# Power_Supplies.net
KiCad netlist of a schematic drawn in Altium Designer
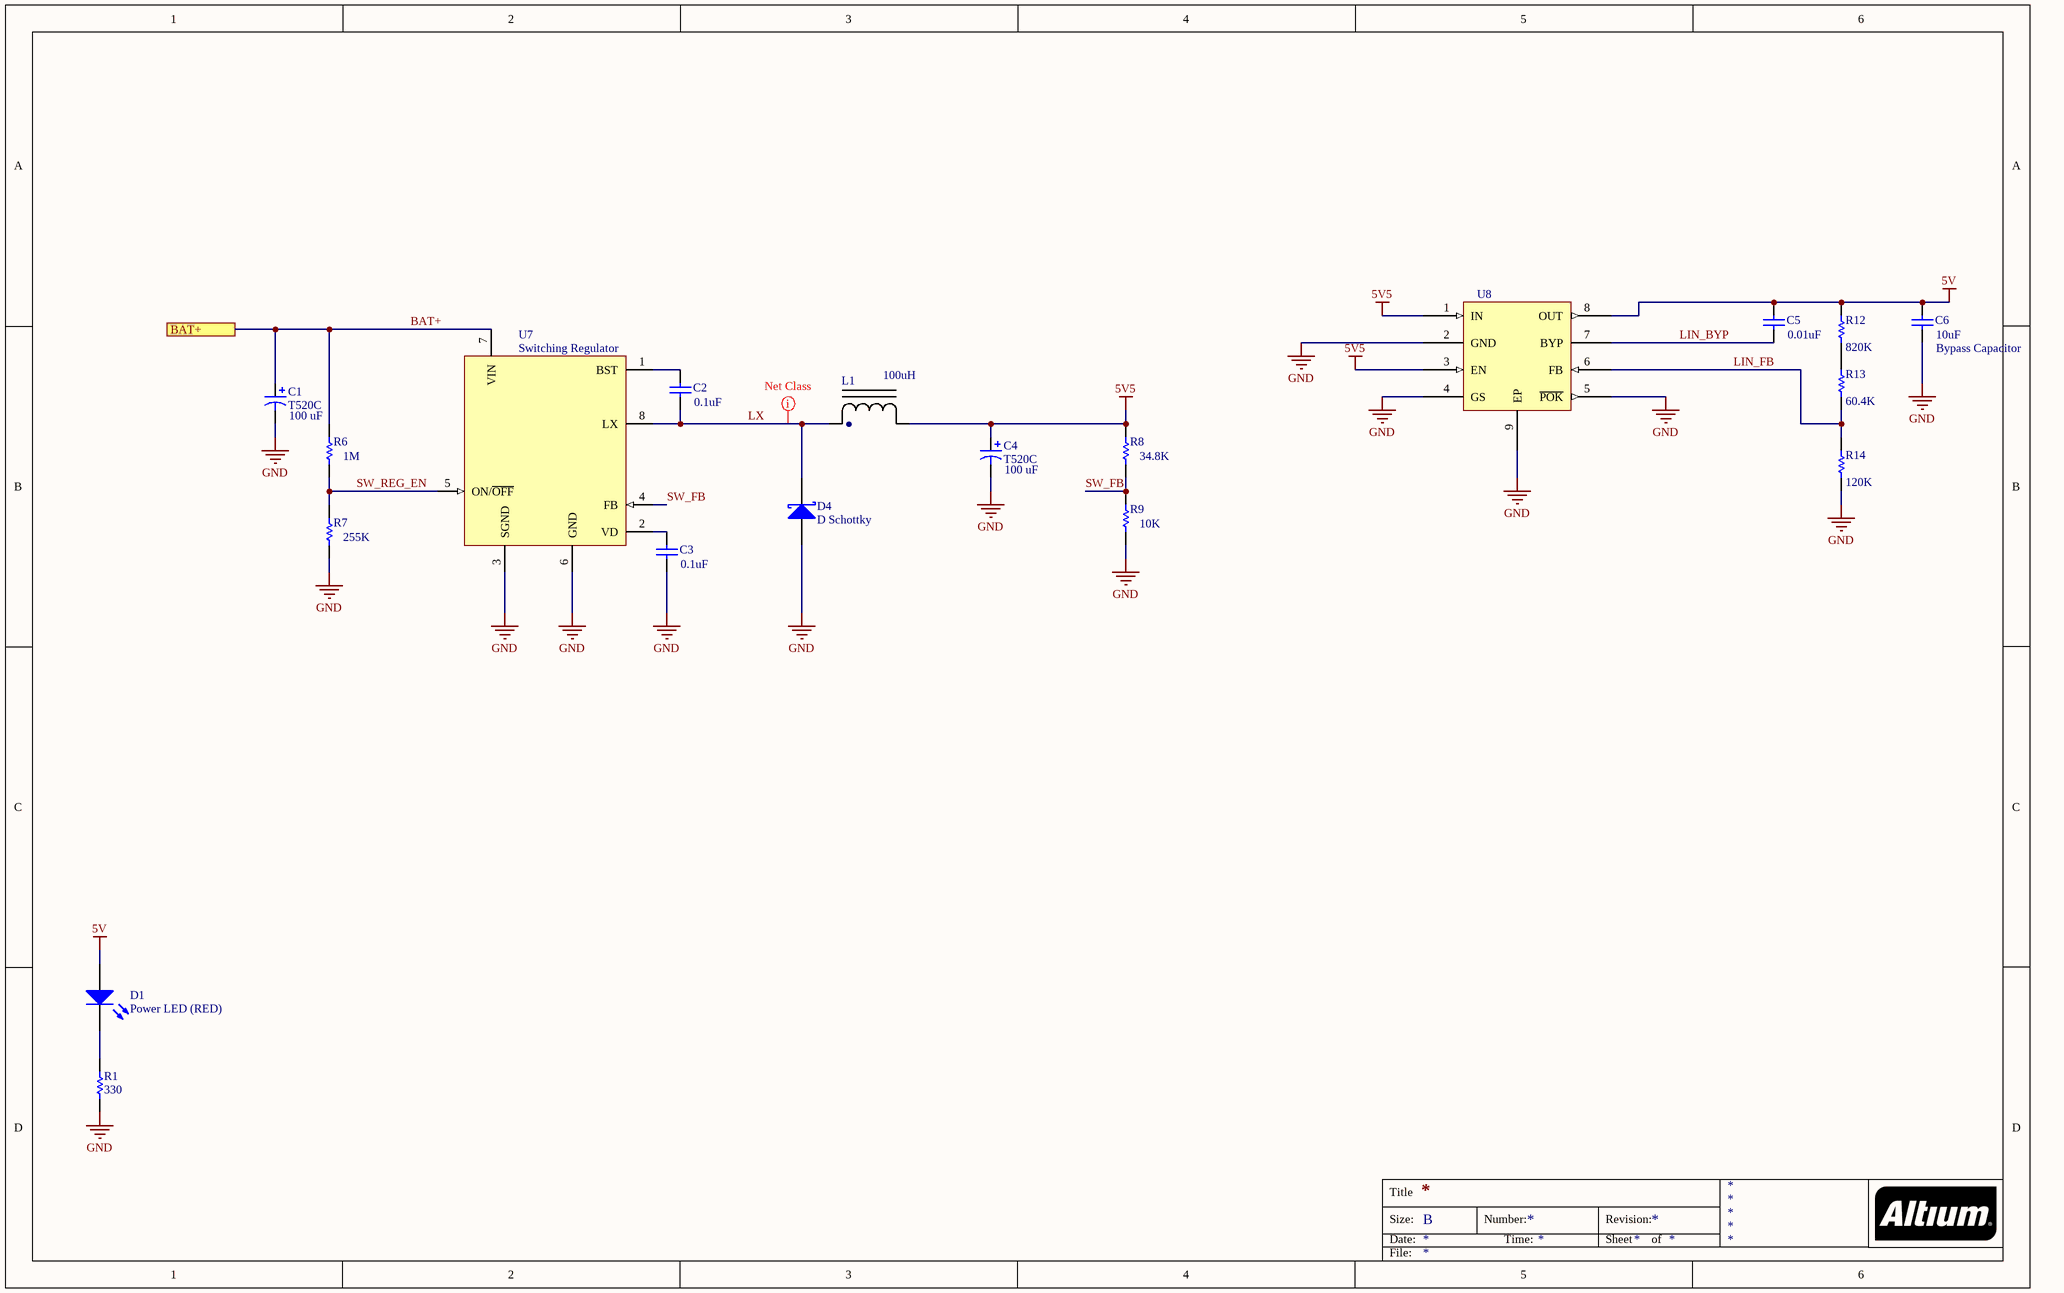
[diagram p0: Power_Supplies.SchDoc]

(export (version "E")
  (design (tool "Eeschema 10.0.6"))
  (components
    (comp (ref "C1")
      (value "T520C")
      (footprint "C")
      (description "Tantalum Capacitors - Polymer SMD 6.3volts 100uF 20% ESR=5mOhms")
      (fields
        (field (name "MANUFACTURER") "KEMET")
        (field (name "TOLERANCE") "20 %")
        (field (name "ALTIUM_VALUE") "100 uF")
      )
      (libsource (lib "KEMET Chip Capacitor") (part "T520D"))
    )
    (comp (ref "C2")
      (value "0.1uF")
      (footprint "1608[0603]")
      (description "Multilayer Ceramic Capacitors MLCC - SMD/SMT 0603 .1uF 50volts X7R 10%")
      (fields
        (field (name "MANUFACTURER PART NUMBER") "VJ0603Y104KXAAC")
        (field (name "MANUFACTURER") "Vishay Semiconductors")
      )
      (libsource (lib "Miscellaneous Devices") (part "Cap"))
    )
    (comp (ref "C3")
      (value "0.1uF")
      (footprint "1608[0603]")
      (description "Multilayer Ceramic Capacitors MLCC - SMD/SMT 0603 .1uF 50volts X7R 10%")
      (fields
        (field (name "MANUFACTURER PART NUMBER") "VJ0603Y104KXAAC")
        (field (name "MANUFACTURER") "Vishay Semiconductors")
      )
      (libsource (lib "Miscellaneous Devices") (part "Cap"))
    )
    (comp (ref "C4")
      (value "T520C")
      (footprint "C")
      (description "Tantalum Capacitors - Polymer SMD 6.3volts 100uF 20% ESR=5mOhms")
      (fields
        (field (name "MANUFACTURER") "KEMET")
        (field (name "TOLERANCE") "20 %")
        (field (name "ALTIUM_VALUE") "100 uF")
      )
      (libsource (lib "KEMET Chip Capacitor") (part "T520D"))
    )
    (comp (ref "C5")
      (value "0.01uF")
      (footprint "1608[0603]")
      (description "Multilayer Ceramic Capacitors MLCC - SMD/SMT 50volts 10000pF X7R 5%")
      (fields
        (field (name "MANUFACTURER PART NUMBER") "C0603C103J5RALTU")
        (field (name "MANUFACTURER") "KEMET")
      )
      (libsource (lib "Miscellaneous Devices") (part "Cap"))
    )
    (comp (ref "C6")
      (value "Bypass Capacitor")
      (footprint "C1206")
      (description "Multilayer Ceramic Capacitors MLCC - SMD/SMT SOFT 1206 25V 10uF X7R 20% T: 1.6mm")
      (fields
        (field (name "ALTIUM_VALUE") "10uF")
        (field (name "MANUFACTURER PART NUMBER") "C3216X7R1E106M160AE")
        (field (name "MANUFACTURER") "TDK")
      )
      (libsource (lib "Miscellaneous Devices") (part "Cap"))
    )
    (comp (ref "D1")
      (value "Power LED (RED)")
      (footprint "1608[0603]")
      (description "Standard LEDs - SMD Super Red, 660nm 1.7V, 45mcd")
      (fields
        (field (name "MANUFACTURER PART NUMBER") "SML-LX0603SRW-TR")
        (field (name "MANUFACTURER") "Lumex")
      )
      (libsource (lib "Miscellaneous Devices") (part "LED0"))
    )
    (comp (ref "D4")
      (value "D Schottky")
      (footprint "SOD123")
      (description "Schottky Diodes & Rectifiers Schottky Power Rect .5a")
      (fields
        (field (name "MANUFACTURER PART NUMBER") "MBR0520L")
        (field (name "MANUFACTURER") "ON Semiconductor / Fairchild")
      )
      (libsource (lib "Miscellaneous Devices") (part "D Schottky"))
    )
    (comp (ref "L1")
      (value "100uH")
      (footprint "UP1B")
      (description "Fixed Inductors 100uH 0.53A 1.11ohms")
      (fields (field (name "TOLERANCE") "20%") (field (name "MANUFACTURER") "Eaton"))
      (libsource (lib "Eaton_Power_Inductors") (part "UP1B-100-R"))
    )
    (comp (ref "R1")
      (value "330")
      (footprint "1608[0603]")
      (description "Thick Film Resistors - SMD 330 ohm 0.5% 0.33W AEC-Q200")
      (fields
        (field (name "MANUFACTURER") "KOA Speer")
        (field (name "MANUFACTURER PART NUMBER") "SG73G1JTTD3300D")
      )
      (libsource (lib "Miscellaneous Devices") (part "Res1"))
    )
    (comp (ref "R6")
      (value "1M")
      (footprint "1608[0603]")
      (description "Thin Film Resistors - SMD 1M OHM .1% 25PPM")
      (fields (field (name "TOLERANCE") "0.1%") (field (name "MANUFACTURER PART NUMBER") "RT0603BRD071ML"))
      (libsource (lib "Miscellaneous Devices") (part "Res1"))
    )
    (comp (ref "R7")
      (value "255K")
      (footprint "1608[0603]")
      (description "Thin Film Resistors - SMD 255Kohms .1% 25ppm")
      (fields (field (name "MANUFACTURER") "Vishay Dale") (field (name "TOLERANCE") "0.1%"))
      (libsource (lib "Miscellaneous Devices") (part "Res1"))
    )
    (comp (ref "R8")
      (value "34.8K")
      (footprint "1608[0603]")
      (description "Thin Film Resistors - SMD 150mW 34.8kohm 0.1% 25PPM 0603")
      (fields (field (name "TOLERANCE") "0.1 %") (field (name "MANUFACTURER") "Vishay"))
      (libsource (lib "Miscellaneous Devices") (part "Res1"))
    )
    (comp (ref "R9")
      (value "10K")
      (footprint "1608[0603]")
      (description "Thin Film Resistors - SMD 150mW 10kohm 0.1% 25PPM 0603")
      (fields (field (name "MANUFACTURER") "Vishay") (field (name "TOLERANCE") "0.1 %"))
      (libsource (lib "Miscellaneous Devices") (part "Res1"))
    )
    (comp (ref "R12")
      (value "820K")
      (footprint "1608[0603]")
      (description "Thin Film Resistors - SMD CPF0603 820K 0.1% 25PPM 5K RL")
      (fields
        (field (name "MANUFACTURER") "TE Connectivity")
        (field (name "MANUFACTURER PART NUMBER") "CPF0603B820KE")
      )
      (libsource (lib "Miscellaneous Devices") (part "Res1"))
    )
    (comp (ref "R13")
      (value "60.4K")
      (footprint "1608[0603]")
      (description "Thin Film Resistors - SMD .063W 60.4K ohm 0.1% 25ppm")
      (fields (field (name "TOLERANCE") "0.1%") (field (name "MANUFACTURER") "TT Welwyn"))
      (libsource (lib "Miscellaneous Devices") (part "Res1"))
    )
    (comp (ref "R14")
      (value "120K")
      (footprint "1608[0603]")
      (description "Thin Film Resistors - SMD CPF 0603 120K 0.1% 25PPM 1K RL")
      (fields (field (name "MANUFACTURER PART NUMBER") "CPF0603B120KE1") (field (name "TOLERANCE") "0.1%"))
      (libsource (lib "Miscellaneous Devices") (part "Res1"))
    )
    (comp (ref "U7")
      (value "Switching Regulator")
      (footprint "SOIC8_N")
      (description "Switching Voltage Regulators 1A 76V MAXPower Step-Down")
      (fields (field (name "MANUFACTURER") "Maxim") (field (name "MANUFACTURER PART NUMBER") "MAX5035DASA+T"))
      (libsource (lib "Maxim_Integrated_Switching_Regulators") (part "MAX5035"))
    )
    (comp (ref "U8")
      (value "MAX8902BATA+T")
      (footprint "8 TDFN-EP")
      (description "LDO Voltage Regulators 500mA LDO Regulator")
      (fields
        (field (name "MANUFACTURER") "Maxim Integrated")
        (field (name "MANUFACTURER PART NUMBER") "MAX8902AATA+T")
      )
      (libsource (lib "Maxim_Integrated_Linear_Regulators") (part "MAX8902BATA+T"))
    )
  )
  (nets
    (net (code "1") (name "/BAT+") (class "Default")
      (node (ref "C1") (pin "1") (pinfunction "1_1") (pintype "passive"))
      (node (ref "R6") (pin "2") (pinfunction "2_2") (pintype "passive"))
      (node (ref "U7") (pin "7") (pinfunction "VIN_7") (pintype "power_in"))
    )
    (net (code "2") (name "/LIN_BYP") (class "Default")
      (node (ref "C5") (pin "1") (pinfunction "1_1") (pintype "passive"))
      (node (ref "U8") (pin "7") (pinfunction "BYP_7") (pintype "passive"))
    )
    (net (code "3") (name "/LIN_FB") (class "Default")
      (node (ref "R13") (pin "1") (pinfunction "1_1") (pintype "passive"))
      (node (ref "R14") (pin "2") (pinfunction "2_2") (pintype "passive"))
      (node (ref "U8") (pin "6") (pinfunction "FB_6") (pintype "input"))
    )
    (net (code "4") (name "/LX") (class "Default")
      (node (ref "C2") (pin "2") (pinfunction "2_2") (pintype "passive"))
      (node (ref "D4") (pin "2") (pinfunction "A_2") (pintype "passive"))
      (node (ref "L1") (pin "1") (pintype "passive"))
      (node (ref "U7") (pin "8") (pinfunction "LX_8") (pintype "passive"))
    )
    (net (code "5") (name "/SW_FB") (class "Default")
      (node (ref "R8") (pin "1") (pinfunction "1_1") (pintype "passive"))
      (node (ref "R9") (pin "2") (pinfunction "2_2") (pintype "passive"))
      (node (ref "U7") (pin "4") (pinfunction "FB_4") (pintype "input"))
    )
    (net (code "6") (name "/SW_REG_EN") (class "Default")
      (node (ref "R6") (pin "1") (pinfunction "1_1") (pintype "passive"))
      (node (ref "R7") (pin "2") (pinfunction "2_2") (pintype "passive"))
      (node (ref "U7") (pin "5") (pinfunction "ON/~{OFF}_5") (pintype "input"))
    )
    (net (code "7") (name "5V") (class "Default")
      (node (ref "C5") (pin "2") (pinfunction "2_2") (pintype "passive"))
      (node (ref "C6") (pin "2") (pinfunction "2_2") (pintype "passive"))
      (node (ref "D1") (pin "1") (pinfunction "A_1") (pintype "passive"))
      (node (ref "R12") (pin "2") (pinfunction "2_2") (pintype "passive"))
      (node (ref "U8") (pin "8") (pinfunction "OUT_8") (pintype "output"))
    )
    (net (code "8") (name "5V5") (class "Default")
      (node (ref "C4") (pin "1") (pinfunction "1_1") (pintype "passive"))
      (node (ref "L1") (pin "2") (pintype "passive"))
      (node (ref "R8") (pin "2") (pinfunction "2_2") (pintype "passive"))
      (node (ref "U8") (pin "1") (pinfunction "IN_1") (pintype "input"))
      (node (ref "U8") (pin "3") (pinfunction "EN_3") (pintype "input"))
    )
    (net (code "9") (name "GND") (class "Default")
      (node (ref "C1") (pin "2") (pinfunction "2_2") (pintype "passive"))
      (node (ref "C3") (pin "2") (pinfunction "2_2") (pintype "passive"))
      (node (ref "C4") (pin "2") (pinfunction "2_2") (pintype "passive"))
      (node (ref "C6") (pin "1") (pinfunction "1_1") (pintype "passive"))
      (node (ref "D4") (pin "1") (pinfunction "K_1") (pintype "passive"))
      (node (ref "R1") (pin "1") (pinfunction "1_1") (pintype "passive"))
      (node (ref "R14") (pin "1") (pinfunction "1_1") (pintype "passive"))
      (node (ref "R7") (pin "1") (pinfunction "1_1") (pintype "passive"))
      (node (ref "R9") (pin "1") (pinfunction "1_1") (pintype "passive"))
      (node (ref "U7") (pin "3") (pinfunction "SGND_3") (pintype "passive"))
      (node (ref "U7") (pin "6") (pinfunction "GND_6") (pintype "passive"))
      (node (ref "U8") (pin "2") (pinfunction "GND_2") (pintype "passive"))
      (node (ref "U8") (pin "4") (pinfunction "GS_4") (pintype "passive"))
      (node (ref "U8") (pin "5") (pinfunction "~{POK}_5") (pintype "output"))
      (node (ref "U8") (pin "9") (pinfunction "EP_9") (pintype "passive"))
    )
    (net (code "10") (name "Net-(D1-K)") (class "Default")
      (node (ref "D1") (pin "2") (pinfunction "K_2") (pintype "passive"))
      (node (ref "R1") (pin "2") (pinfunction "2_2") (pintype "passive"))
    )
    (net (code "11") (name "Net-(R12-Pad1)") (class "Default")
      (node (ref "R12") (pin "1") (pinfunction "1_1") (pintype "passive"))
      (node (ref "R13") (pin "2") (pinfunction "2_2") (pintype "passive"))
    )
    (net (code "12") (name "Net-(U7-BST)") (class "Default")
      (node (ref "C2") (pin "1") (pinfunction "1_1") (pintype "passive"))
      (node (ref "U7") (pin "1") (pinfunction "BST_1") (pintype "passive"))
    )
    (net (code "13") (name "Net-(U7-VD)") (class "Default")
      (node (ref "C3") (pin "1") (pinfunction "1_1") (pintype "passive"))
      (node (ref "U7") (pin "2") (pinfunction "VD_2") (pintype "power_in"))
    )
  )
)
